# mainboard.net
KiCad netlist of a schematic drawn in EAGLE
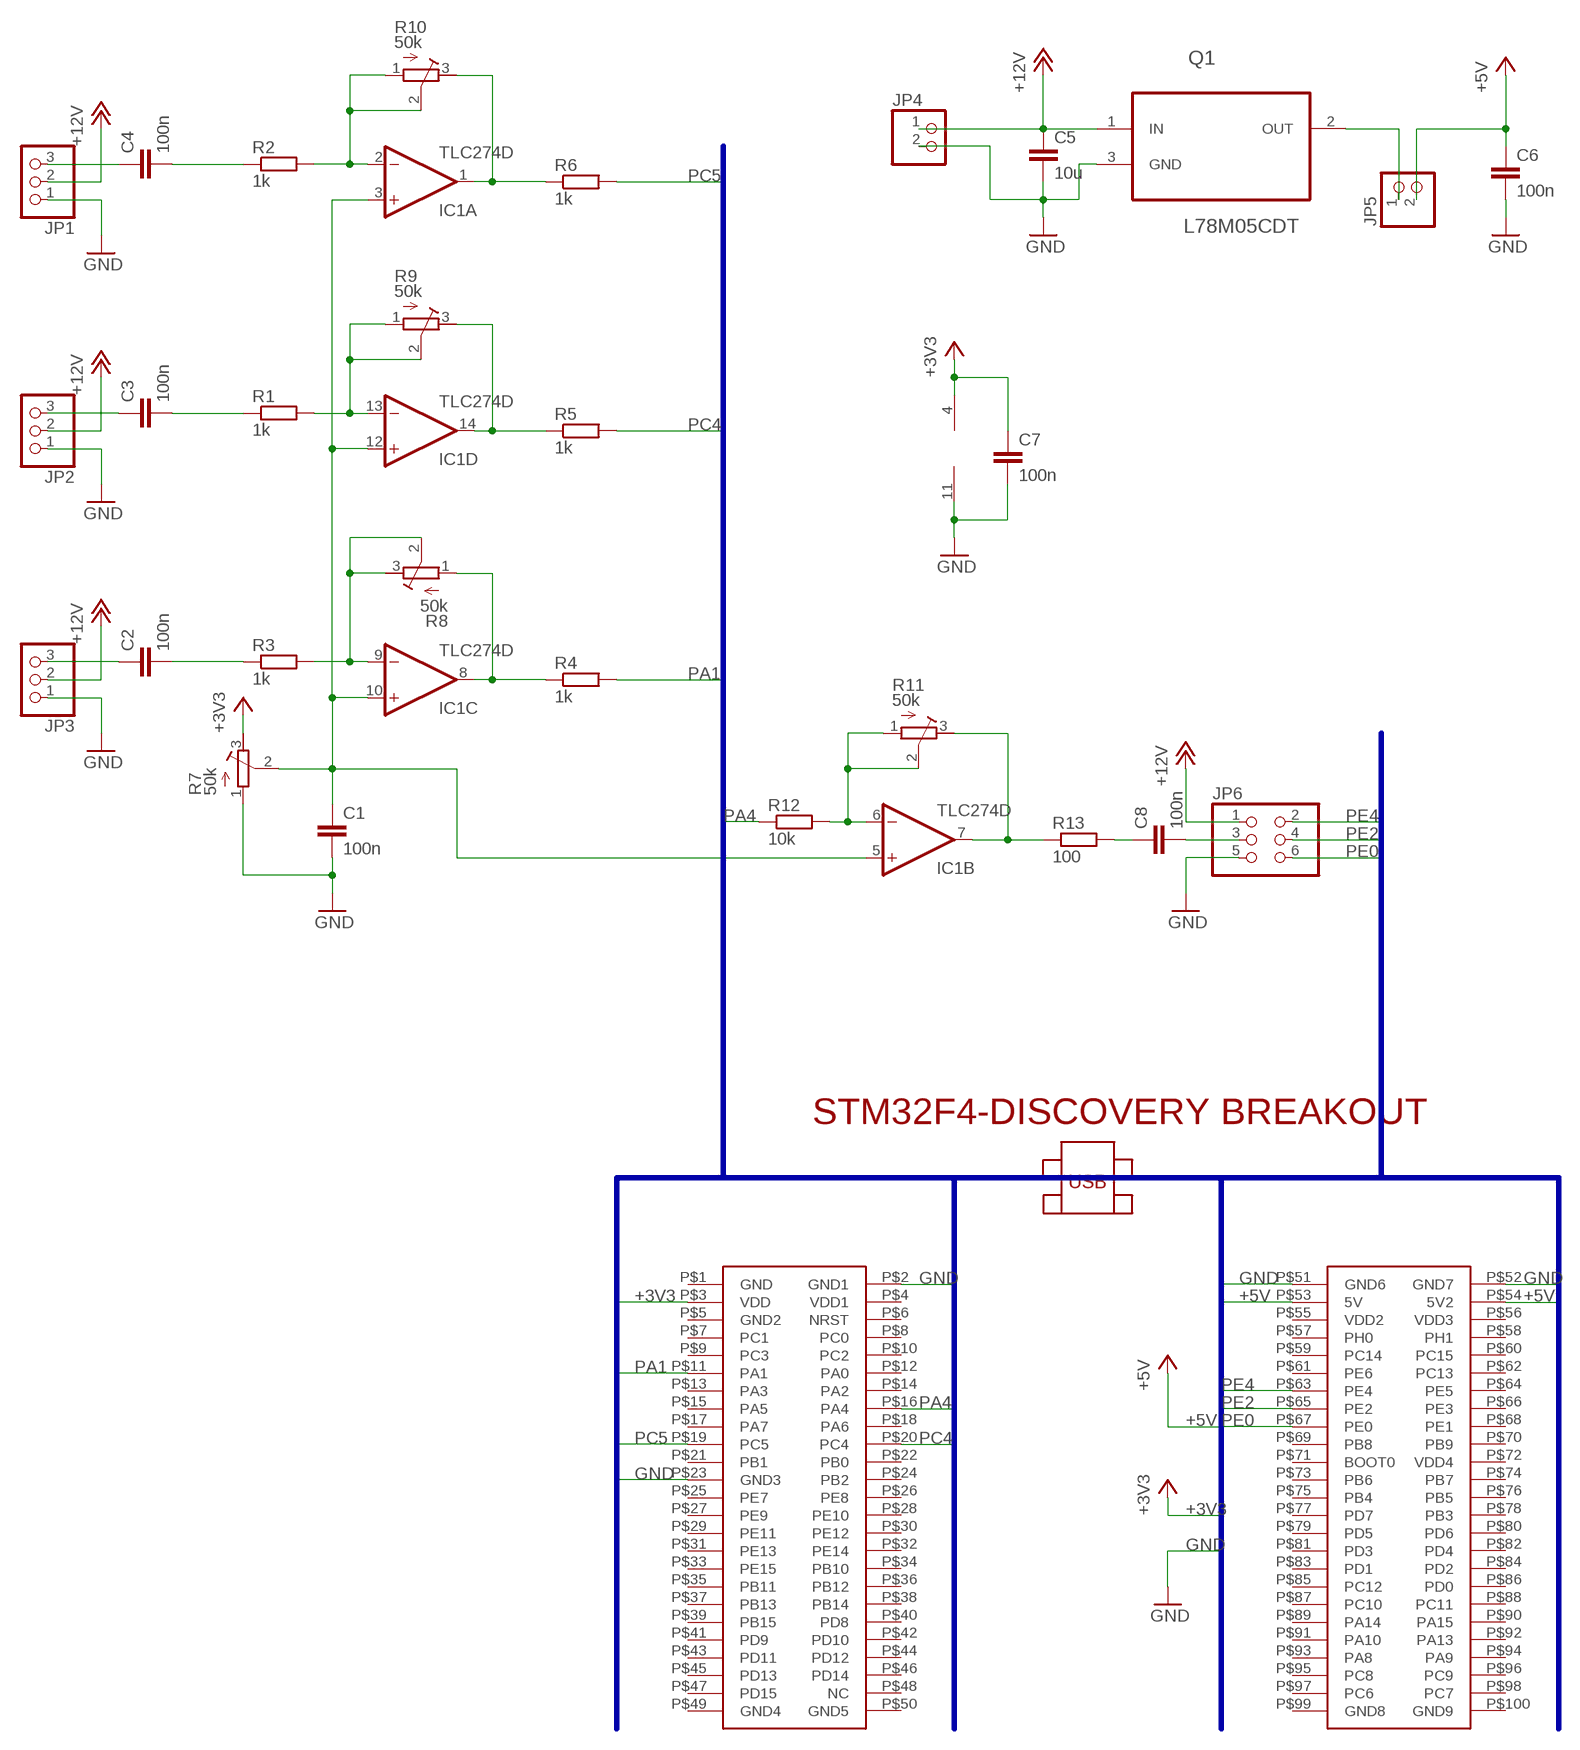
[diagram p0: schematic, sheet 1]

(export (version "E")
  (design (tool "Eeschema 10.0.6"))
  (components
    (comp (ref "C1")
      (value "100n")
      (footprint "eagle-import:C1206K")
      (libsource (lib "eagle-import") (part "C-EUC1206K"))
    )
    (comp (ref "C2")
      (value "100n")
      (footprint "eagle-import:C1206K")
      (libsource (lib "eagle-import") (part "C-EUC1206K"))
    )
    (comp (ref "C3")
      (value "100n")
      (footprint "eagle-import:C1206K")
      (libsource (lib "eagle-import") (part "C-EUC1206K"))
    )
    (comp (ref "C4")
      (value "100n")
      (footprint "eagle-import:C1206K")
      (libsource (lib "eagle-import") (part "C-EUC1206K"))
    )
    (comp (ref "C5")
      (value "10u")
      (footprint "eagle-import:C1206K")
      (libsource (lib "eagle-import") (part "C-EUC1206K"))
    )
    (comp (ref "C6")
      (value "100n")
      (footprint "eagle-import:C1206K")
      (libsource (lib "eagle-import") (part "C-EUC1206K"))
    )
    (comp (ref "C7")
      (value "100n")
      (footprint "eagle-import:C1206K")
      (libsource (lib "eagle-import") (part "C-EUC1206K"))
    )
    (comp (ref "C8")
      (value "100n")
      (footprint "eagle-import:C1206K")
      (libsource (lib "eagle-import") (part "C-EUC1206K"))
    )
    (comp (ref "IC1")
      (value "TLC274D")
      (footprint "eagle-import:SO14")
      (libsource (lib "eagle-import") (part "TLC274D"))
    )
    (comp (ref "JP1")
      (value "PINHD-1X3")
      (footprint "eagle-import:1X03")
      (libsource (lib "eagle-import") (part "PINHD-1X3"))
    )
    (comp (ref "JP2")
      (value "PINHD-1X3")
      (footprint "eagle-import:1X03")
      (libsource (lib "eagle-import") (part "PINHD-1X3"))
    )
    (comp (ref "JP3")
      (value "PINHD-1X3")
      (footprint "eagle-import:1X03")
      (libsource (lib "eagle-import") (part "PINHD-1X3"))
    )
    (comp (ref "JP4")
      (value "PINHD-1X2")
      (footprint "eagle-import:1X02")
      (libsource (lib "eagle-import") (part "PINHD-1X2"))
    )
    (comp (ref "JP5")
      (value "PINHD-1X2")
      (footprint "eagle-import:1X02")
      (libsource (lib "eagle-import") (part "PINHD-1X2"))
    )
    (comp (ref "JP6")
      (value "PINHD-2X3")
      (footprint "eagle-import:2X03")
      (libsource (lib "eagle-import") (part "PINHD-2X3"))
    )
    (comp (ref "Q1")
      (value "L78M05CDT")
      (footprint "eagle-import:TO225P972X240-3N")
      (libsource (lib "eagle-import") (part "L78M05CDT"))
    )
    (comp (ref "R1")
      (value "1k")
      (footprint "eagle-import:M0805")
      (libsource (lib "eagle-import") (part "R-EU_M0805"))
    )
    (comp (ref "R2")
      (value "1k")
      (footprint "eagle-import:M0805")
      (libsource (lib "eagle-import") (part "R-EU_M0805"))
    )
    (comp (ref "R3")
      (value "1k")
      (footprint "eagle-import:M0805")
      (libsource (lib "eagle-import") (part "R-EU_M0805"))
    )
    (comp (ref "R4")
      (value "1k")
      (footprint "eagle-import:M0805")
      (libsource (lib "eagle-import") (part "R-EU_M0805"))
    )
    (comp (ref "R5")
      (value "1k")
      (footprint "eagle-import:R1206")
      (libsource (lib "eagle-import") (part "R-EU_R1206"))
    )
    (comp (ref "R6")
      (value "1k")
      (footprint "eagle-import:M0805")
      (libsource (lib "eagle-import") (part "R-EU_M0805"))
    )
    (comp (ref "R7")
      (value "50k")
      (footprint "eagle-import:RTRIM3314J")
      (libsource (lib "eagle-import") (part "R-TRIMM3314J"))
    )
    (comp (ref "R8")
      (value "50k")
      (footprint "eagle-import:RTRIM3314J")
      (libsource (lib "eagle-import") (part "R-TRIMM3314J"))
    )
    (comp (ref "R9")
      (value "50k")
      (footprint "eagle-import:RTRIM3314J")
      (libsource (lib "eagle-import") (part "R-TRIMM3314J"))
    )
    (comp (ref "R10")
      (value "50k")
      (footprint "eagle-import:RTRIM3314J")
      (libsource (lib "eagle-import") (part "R-TRIMM3314J"))
    )
    (comp (ref "R11")
      (value "50k")
      (footprint "eagle-import:RTRIM3314J")
      (libsource (lib "eagle-import") (part "R-TRIMM3314J"))
    )
    (comp (ref "R12")
      (value "10k")
      (footprint "eagle-import:M1206")
      (libsource (lib "eagle-import") (part "R-EU_M1206"))
    )
    (comp (ref "R13")
      (value "100")
      (footprint "eagle-import:M0805")
      (libsource (lib "eagle-import") (part "R-EU_M0805"))
    )
    (comp (ref "U$1")
      (value "STM32F4-DISCOVERY")
      (footprint "eagle-import:STM32F4-DISCOVERY")
      (libsource (lib "eagle-import") (part "STM32F4-DISCOVERY"))
    )
  )
  (nets
    (net (code "1") (name "+3V3") (class "Default")
      (node (ref "C7") (pin "1") (pinfunction "1_1") (pintype "passive"))
      (node (ref "IC1") (pin "4") (pinfunction "V+_4") (pintype "power_in"))
      (node (ref "R7") (pin "3") (pinfunction "A_3") (pintype "passive"))
      (node (ref "U$1") (pin "P$3") (pinfunction "VDD_P$3") (pintype "bidirectional"))
    )
    (net (code "2") (name "+5V") (class "Default")
      (node (ref "C6") (pin "1") (pinfunction "1_1") (pintype "passive"))
      (node (ref "JP5") (pin "2") (pinfunction "2_2") (pintype "passive"))
      (node (ref "U$1") (pin "P$53") (pinfunction "5V_P$53") (pintype "bidirectional"))
      (node (ref "U$1") (pin "P$54") (pinfunction "5V2_P$54") (pintype "bidirectional"))
    )
    (net (code "3") (name "+12V") (class "Default")
      (node (ref "C5") (pin "1") (pinfunction "1_1") (pintype "passive"))
      (node (ref "JP1") (pin "2") (pinfunction "2_2") (pintype "passive"))
      (node (ref "JP2") (pin "2") (pinfunction "2_2") (pintype "passive"))
      (node (ref "JP3") (pin "2") (pinfunction "2_2") (pintype "passive"))
      (node (ref "JP4") (pin "1") (pinfunction "1_1") (pintype "passive"))
      (node (ref "JP6") (pin "1") (pinfunction "1_1") (pintype "passive"))
      (node (ref "Q1") (pin "1") (pinfunction "IN_1") (pintype "input"))
    )
    (net (code "4") (name "/PA1") (class "Default")
      (node (ref "R4") (pin "2") (pinfunction "2_2") (pintype "passive"))
      (node (ref "U$1") (pin "P$11") (pinfunction "PA1_P$11") (pintype "bidirectional"))
    )
    (net (code "5") (name "/PA4") (class "Default")
      (node (ref "R12") (pin "1") (pinfunction "1_1") (pintype "passive"))
      (node (ref "U$1") (pin "P$16") (pinfunction "PA4_P$16") (pintype "bidirectional"))
    )
    (net (code "6") (name "/PC4") (class "Default")
      (node (ref "R5") (pin "2") (pinfunction "2_2") (pintype "passive"))
      (node (ref "U$1") (pin "P$20") (pinfunction "PC4_P$20") (pintype "bidirectional"))
    )
    (net (code "7") (name "/PC5") (class "Default")
      (node (ref "R6") (pin "2") (pinfunction "2_2") (pintype "passive"))
      (node (ref "U$1") (pin "P$19") (pinfunction "PC5_P$19") (pintype "bidirectional"))
    )
    (net (code "8") (name "/PE0") (class "Default")
      (node (ref "JP6") (pin "6") (pinfunction "6_6") (pintype "passive"))
      (node (ref "U$1") (pin "P$67") (pinfunction "PE0_P$67") (pintype "bidirectional"))
    )
    (net (code "9") (name "/PE2") (class "Default")
      (node (ref "JP6") (pin "4") (pinfunction "4_4") (pintype "passive"))
      (node (ref "U$1") (pin "P$65") (pinfunction "PE2_P$65") (pintype "bidirectional"))
    )
    (net (code "10") (name "/PE4") (class "Default")
      (node (ref "JP6") (pin "2") (pinfunction "2_2") (pintype "passive"))
      (node (ref "U$1") (pin "P$63") (pinfunction "PE4_P$63") (pintype "bidirectional"))
    )
    (net (code "11") (name "GND") (class "Default")
      (node (ref "C1") (pin "2") (pinfunction "2_2") (pintype "passive"))
      (node (ref "C5") (pin "2") (pinfunction "2_2") (pintype "passive"))
      (node (ref "C6") (pin "2") (pinfunction "2_2") (pintype "passive"))
      (node (ref "C7") (pin "2") (pinfunction "2_2") (pintype "passive"))
      (node (ref "IC1") (pin "11") (pinfunction "V-_11") (pintype "power_in"))
      (node (ref "JP1") (pin "1") (pinfunction "1_1") (pintype "passive"))
      (node (ref "JP2") (pin "1") (pinfunction "1_1") (pintype "passive"))
      (node (ref "JP3") (pin "1") (pinfunction "1_1") (pintype "passive"))
      (node (ref "JP4") (pin "2") (pinfunction "2_2") (pintype "passive"))
      (node (ref "JP6") (pin "5") (pinfunction "5_5") (pintype "passive"))
      (node (ref "Q1") (pin "3") (pinfunction "GND_3") (pintype "passive"))
      (node (ref "R7") (pin "1") (pinfunction "E_1") (pintype "passive"))
      (node (ref "U$1") (pin "P$2") (pinfunction "GND1_P$2") (pintype "bidirectional"))
      (node (ref "U$1") (pin "P$23") (pinfunction "GND3_P$23") (pintype "bidirectional"))
      (node (ref "U$1") (pin "P$51") (pinfunction "GND6_P$51") (pintype "bidirectional"))
      (node (ref "U$1") (pin "P$52") (pinfunction "GND7_P$52") (pintype "bidirectional"))
    )
    (net (code "12") (name "Net-(C2-Pad1)") (class "Default")
      (node (ref "C2") (pin "1") (pinfunction "1_1") (pintype "passive"))
      (node (ref "JP3") (pin "3") (pinfunction "3_3") (pintype "passive"))
    )
    (net (code "13") (name "Net-(C2-Pad2)") (class "Default")
      (node (ref "C2") (pin "2") (pinfunction "2_2") (pintype "passive"))
      (node (ref "R3") (pin "1") (pinfunction "1_1") (pintype "passive"))
    )
    (net (code "14") (name "Net-(C3-Pad1)") (class "Default")
      (node (ref "C3") (pin "1") (pinfunction "1_1") (pintype "passive"))
      (node (ref "JP2") (pin "3") (pinfunction "3_3") (pintype "passive"))
    )
    (net (code "15") (name "Net-(C3-Pad2)") (class "Default")
      (node (ref "C3") (pin "2") (pinfunction "2_2") (pintype "passive"))
      (node (ref "R1") (pin "1") (pinfunction "1_1") (pintype "passive"))
    )
    (net (code "16") (name "Net-(C4-Pad1)") (class "Default")
      (node (ref "C4") (pin "1") (pinfunction "1_1") (pintype "passive"))
      (node (ref "JP1") (pin "3") (pinfunction "3_3") (pintype "passive"))
    )
    (net (code "17") (name "Net-(C4-Pad2)") (class "Default")
      (node (ref "C4") (pin "2") (pinfunction "2_2") (pintype "passive"))
      (node (ref "R2") (pin "1") (pinfunction "1_1") (pintype "passive"))
    )
    (net (code "18") (name "Net-(C8-Pad1)") (class "Default")
      (node (ref "C8") (pin "1") (pinfunction "1_1") (pintype "passive"))
      (node (ref "R13") (pin "2") (pinfunction "2_2") (pintype "passive"))
    )
    (net (code "19") (name "Net-(C8-Pad2)") (class "Default")
      (node (ref "C8") (pin "2") (pinfunction "2_2") (pintype "passive"))
      (node (ref "JP6") (pin "3") (pinfunction "3_3") (pintype "passive"))
    )
    (net (code "20") (name "Net-(IC1A-+IN)") (class "Default")
      (node (ref "C1") (pin "1") (pinfunction "1_1") (pintype "passive"))
      (node (ref "IC1") (pin "10") (pinfunction "+IN_10") (pintype "input"))
      (node (ref "IC1") (pin "12") (pinfunction "+IN_12") (pintype "input"))
      (node (ref "IC1") (pin "3") (pinfunction "+IN_3") (pintype "input"))
      (node (ref "IC1") (pin "5") (pinfunction "+IN_5") (pintype "input"))
      (node (ref "R7") (pin "2") (pinfunction "S_2") (pintype "passive"))
    )
    (net (code "21") (name "Net-(IC1A--IN)") (class "Default")
      (node (ref "IC1") (pin "2") (pinfunction "-IN_2") (pintype "input"))
      (node (ref "R10") (pin "1") (pinfunction "E_1") (pintype "passive"))
      (node (ref "R10") (pin "2") (pinfunction "S_2") (pintype "passive"))
      (node (ref "R2") (pin "2") (pinfunction "2_2") (pintype "passive"))
    )
    (net (code "22") (name "Net-(IC1A-OUT)") (class "Default")
      (node (ref "IC1") (pin "1") (pinfunction "OUT_1") (pintype "output"))
      (node (ref "R10") (pin "3") (pinfunction "A_3") (pintype "passive"))
      (node (ref "R6") (pin "1") (pinfunction "1_1") (pintype "passive"))
    )
    (net (code "23") (name "Net-(IC1B--IN)") (class "Default")
      (node (ref "IC1") (pin "6") (pinfunction "-IN_6") (pintype "input"))
      (node (ref "R11") (pin "1") (pinfunction "E_1") (pintype "passive"))
      (node (ref "R11") (pin "2") (pinfunction "S_2") (pintype "passive"))
      (node (ref "R12") (pin "2") (pinfunction "2_2") (pintype "passive"))
    )
    (net (code "24") (name "Net-(IC1B-OUT)") (class "Default")
      (node (ref "IC1") (pin "7") (pinfunction "OUT_7") (pintype "output"))
      (node (ref "R11") (pin "3") (pinfunction "A_3") (pintype "passive"))
      (node (ref "R13") (pin "1") (pinfunction "1_1") (pintype "passive"))
    )
    (net (code "25") (name "Net-(IC1C--IN)") (class "Default")
      (node (ref "IC1") (pin "9") (pinfunction "-IN_9") (pintype "input"))
      (node (ref "R3") (pin "2") (pinfunction "2_2") (pintype "passive"))
      (node (ref "R8") (pin "2") (pinfunction "S_2") (pintype "passive"))
      (node (ref "R8") (pin "3") (pinfunction "A_3") (pintype "passive"))
    )
    (net (code "26") (name "Net-(IC1C-OUT)") (class "Default")
      (node (ref "IC1") (pin "8") (pinfunction "OUT_8") (pintype "output"))
      (node (ref "R4") (pin "1") (pinfunction "1_1") (pintype "passive"))
      (node (ref "R8") (pin "1") (pinfunction "E_1") (pintype "passive"))
    )
    (net (code "27") (name "Net-(IC1D--IN)") (class "Default")
      (node (ref "IC1") (pin "13") (pinfunction "-IN_13") (pintype "input"))
      (node (ref "R1") (pin "2") (pinfunction "2_2") (pintype "passive"))
      (node (ref "R9") (pin "1") (pinfunction "E_1") (pintype "passive"))
      (node (ref "R9") (pin "2") (pinfunction "S_2") (pintype "passive"))
    )
    (net (code "28") (name "Net-(IC1D-OUT)") (class "Default")
      (node (ref "IC1") (pin "14") (pinfunction "OUT_14") (pintype "output"))
      (node (ref "R5") (pin "1") (pinfunction "1_1") (pintype "passive"))
      (node (ref "R9") (pin "3") (pinfunction "A_3") (pintype "passive"))
    )
    (net (code "29") (name "Net-(Q1-OUT)") (class "Default")
      (node (ref "JP5") (pin "1") (pinfunction "1_1") (pintype "passive"))
      (node (ref "Q1") (pin "2") (pinfunction "OUT_2") (pintype "output"))
    )
    (net (code "30") (name "unconnected-(U$1-BOOT0-PadP$71)") (class "Default")
      (node (ref "U$1") (pin "P$71") (pinfunction "BOOT0_P$71") (pintype "bidirectional"))
    )
    (net (code "31") (name "unconnected-(U$1-GND-PadP$1)") (class "Default")
      (node (ref "U$1") (pin "P$1") (pinfunction "GND_P$1") (pintype "bidirectional"))
    )
    (net (code "32") (name "unconnected-(U$1-GND2-PadP$5)") (class "Default")
      (node (ref "U$1") (pin "P$5") (pinfunction "GND2_P$5") (pintype "bidirectional"))
    )
    (net (code "33") (name "unconnected-(U$1-GND4-PadP$49)") (class "Default")
      (node (ref "U$1") (pin "P$49") (pinfunction "GND4_P$49") (pintype "bidirectional"))
    )
    (net (code "34") (name "unconnected-(U$1-GND5-PadP$50)") (class "Default")
      (node (ref "U$1") (pin "P$50") (pinfunction "GND5_P$50") (pintype "bidirectional"))
    )
    (net (code "35") (name "unconnected-(U$1-GND8-PadP$99)") (class "Default")
      (node (ref "U$1") (pin "P$99") (pinfunction "GND8_P$99") (pintype "bidirectional"))
    )
    (net (code "36") (name "unconnected-(U$1-GND9-PadP$100)") (class "Default")
      (node (ref "U$1") (pin "P$100") (pinfunction "GND9_P$100") (pintype "bidirectional"))
    )
    (net (code "37") (name "unconnected-(U$1-NC-PadP$48)") (class "Default")
      (node (ref "U$1") (pin "P$48") (pinfunction "NC_P$48") (pintype "bidirectional"))
    )
    (net (code "38") (name "unconnected-(U$1-NRST-PadP$6)") (class "Default")
      (node (ref "U$1") (pin "P$6") (pinfunction "NRST_P$6") (pintype "bidirectional"))
    )
    (net (code "39") (name "unconnected-(U$1-PA0-PadP$12)") (class "Default")
      (node (ref "U$1") (pin "P$12") (pinfunction "PA0_P$12") (pintype "bidirectional"))
    )
    (net (code "40") (name "unconnected-(U$1-PA2-PadP$14)") (class "Default")
      (node (ref "U$1") (pin "P$14") (pinfunction "PA2_P$14") (pintype "bidirectional"))
    )
    (net (code "41") (name "unconnected-(U$1-PA3-PadP$13)") (class "Default")
      (node (ref "U$1") (pin "P$13") (pinfunction "PA3_P$13") (pintype "bidirectional"))
    )
    (net (code "42") (name "unconnected-(U$1-PA5-PadP$15)") (class "Default")
      (node (ref "U$1") (pin "P$15") (pinfunction "PA5_P$15") (pintype "bidirectional"))
    )
    (net (code "43") (name "unconnected-(U$1-PA6-PadP$18)") (class "Default")
      (node (ref "U$1") (pin "P$18") (pinfunction "PA6_P$18") (pintype "bidirectional"))
    )
    (net (code "44") (name "unconnected-(U$1-PA7-PadP$17)") (class "Default")
      (node (ref "U$1") (pin "P$17") (pinfunction "PA7_P$17") (pintype "bidirectional"))
    )
    (net (code "45") (name "unconnected-(U$1-PA8-PadP$93)") (class "Default")
      (node (ref "U$1") (pin "P$93") (pinfunction "PA8_P$93") (pintype "bidirectional"))
    )
    (net (code "46") (name "unconnected-(U$1-PA9-PadP$94)") (class "Default")
      (node (ref "U$1") (pin "P$94") (pinfunction "PA9_P$94") (pintype "bidirectional"))
    )
    (net (code "47") (name "unconnected-(U$1-PA10-PadP$91)") (class "Default")
      (node (ref "U$1") (pin "P$91") (pinfunction "PA10_P$91") (pintype "bidirectional"))
    )
    (net (code "48") (name "unconnected-(U$1-PA13-PadP$92)") (class "Default")
      (node (ref "U$1") (pin "P$92") (pinfunction "PA13_P$92") (pintype "bidirectional"))
    )
    (net (code "49") (name "unconnected-(U$1-PA14-PadP$89)") (class "Default")
      (node (ref "U$1") (pin "P$89") (pinfunction "PA14_P$89") (pintype "bidirectional"))
    )
    (net (code "50") (name "unconnected-(U$1-PA15-PadP$90)") (class "Default")
      (node (ref "U$1") (pin "P$90") (pinfunction "PA15_P$90") (pintype "bidirectional"))
    )
    (net (code "51") (name "unconnected-(U$1-PB0-PadP$22)") (class "Default")
      (node (ref "U$1") (pin "P$22") (pinfunction "PB0_P$22") (pintype "bidirectional"))
    )
    (net (code "52") (name "unconnected-(U$1-PB1-PadP$21)") (class "Default")
      (node (ref "U$1") (pin "P$21") (pinfunction "PB1_P$21") (pintype "bidirectional"))
    )
    (net (code "53") (name "unconnected-(U$1-PB2-PadP$24)") (class "Default")
      (node (ref "U$1") (pin "P$24") (pinfunction "PB2_P$24") (pintype "bidirectional"))
    )
    (net (code "54") (name "unconnected-(U$1-PB3-PadP$78)") (class "Default")
      (node (ref "U$1") (pin "P$78") (pinfunction "PB3_P$78") (pintype "bidirectional"))
    )
    (net (code "55") (name "unconnected-(U$1-PB4-PadP$75)") (class "Default")
      (node (ref "U$1") (pin "P$75") (pinfunction "PB4_P$75") (pintype "bidirectional"))
    )
    (net (code "56") (name "unconnected-(U$1-PB5-PadP$76)") (class "Default")
      (node (ref "U$1") (pin "P$76") (pinfunction "PB5_P$76") (pintype "bidirectional"))
    )
    (net (code "57") (name "unconnected-(U$1-PB6-PadP$73)") (class "Default")
      (node (ref "U$1") (pin "P$73") (pinfunction "PB6_P$73") (pintype "bidirectional"))
    )
    (net (code "58") (name "unconnected-(U$1-PB7-PadP$74)") (class "Default")
      (node (ref "U$1") (pin "P$74") (pinfunction "PB7_P$74") (pintype "bidirectional"))
    )
    (net (code "59") (name "unconnected-(U$1-PB8-PadP$69)") (class "Default")
      (node (ref "U$1") (pin "P$69") (pinfunction "PB8_P$69") (pintype "bidirectional"))
    )
    (net (code "60") (name "unconnected-(U$1-PB9-PadP$70)") (class "Default")
      (node (ref "U$1") (pin "P$70") (pinfunction "PB9_P$70") (pintype "bidirectional"))
    )
    (net (code "61") (name "unconnected-(U$1-PB10-PadP$34)") (class "Default")
      (node (ref "U$1") (pin "P$34") (pinfunction "PB10_P$34") (pintype "bidirectional"))
    )
    (net (code "62") (name "unconnected-(U$1-PB11-PadP$35)") (class "Default")
      (node (ref "U$1") (pin "P$35") (pinfunction "PB11_P$35") (pintype "bidirectional"))
    )
    (net (code "63") (name "unconnected-(U$1-PB12-PadP$36)") (class "Default")
      (node (ref "U$1") (pin "P$36") (pinfunction "PB12_P$36") (pintype "bidirectional"))
    )
    (net (code "64") (name "unconnected-(U$1-PB13-PadP$37)") (class "Default")
      (node (ref "U$1") (pin "P$37") (pinfunction "PB13_P$37") (pintype "bidirectional"))
    )
    (net (code "65") (name "unconnected-(U$1-PB14-PadP$38)") (class "Default")
      (node (ref "U$1") (pin "P$38") (pinfunction "PB14_P$38") (pintype "bidirectional"))
    )
    (net (code "66") (name "unconnected-(U$1-PB15-PadP$39)") (class "Default")
      (node (ref "U$1") (pin "P$39") (pinfunction "PB15_P$39") (pintype "bidirectional"))
    )
    (net (code "67") (name "unconnected-(U$1-PC0-PadP$8)") (class "Default")
      (node (ref "U$1") (pin "P$8") (pinfunction "PC0_P$8") (pintype "bidirectional"))
    )
    (net (code "68") (name "unconnected-(U$1-PC1-PadP$7)") (class "Default")
      (node (ref "U$1") (pin "P$7") (pinfunction "PC1_P$7") (pintype "bidirectional"))
    )
    (net (code "69") (name "unconnected-(U$1-PC2-PadP$10)") (class "Default")
      (node (ref "U$1") (pin "P$10") (pinfunction "PC2_P$10") (pintype "bidirectional"))
    )
    (net (code "70") (name "unconnected-(U$1-PC3-PadP$9)") (class "Default")
      (node (ref "U$1") (pin "P$9") (pinfunction "PC3_P$9") (pintype "bidirectional"))
    )
    (net (code "71") (name "unconnected-(U$1-PC6-PadP$97)") (class "Default")
      (node (ref "U$1") (pin "P$97") (pinfunction "PC6_P$97") (pintype "bidirectional"))
    )
    (net (code "72") (name "unconnected-(U$1-PC7-PadP$98)") (class "Default")
      (node (ref "U$1") (pin "P$98") (pinfunction "PC7_P$98") (pintype "bidirectional"))
    )
    (net (code "73") (name "unconnected-(U$1-PC8-PadP$95)") (class "Default")
      (node (ref "U$1") (pin "P$95") (pinfunction "PC8_P$95") (pintype "bidirectional"))
    )
    (net (code "74") (name "unconnected-(U$1-PC9-PadP$96)") (class "Default")
      (node (ref "U$1") (pin "P$96") (pinfunction "PC9_P$96") (pintype "bidirectional"))
    )
    (net (code "75") (name "unconnected-(U$1-PC10-PadP$87)") (class "Default")
      (node (ref "U$1") (pin "P$87") (pinfunction "PC10_P$87") (pintype "bidirectional"))
    )
    (net (code "76") (name "unconnected-(U$1-PC11-PadP$88)") (class "Default")
      (node (ref "U$1") (pin "P$88") (pinfunction "PC11_P$88") (pintype "bidirectional"))
    )
    (net (code "77") (name "unconnected-(U$1-PC12-PadP$85)") (class "Default")
      (node (ref "U$1") (pin "P$85") (pinfunction "PC12_P$85") (pintype "bidirectional"))
    )
    (net (code "78") (name "unconnected-(U$1-PC13-PadP$62)") (class "Default")
      (node (ref "U$1") (pin "P$62") (pinfunction "PC13_P$62") (pintype "bidirectional"))
    )
    (net (code "79") (name "unconnected-(U$1-PC14-PadP$59)") (class "Default")
      (node (ref "U$1") (pin "P$59") (pinfunction "PC14_P$59") (pintype "bidirectional"))
    )
    (net (code "80") (name "unconnected-(U$1-PC15-PadP$60)") (class "Default")
      (node (ref "U$1") (pin "P$60") (pinfunction "PC15_P$60") (pintype "bidirectional"))
    )
    (net (code "81") (name "unconnected-(U$1-PD0-PadP$86)") (class "Default")
      (node (ref "U$1") (pin "P$86") (pinfunction "PD0_P$86") (pintype "bidirectional"))
    )
    (net (code "82") (name "unconnected-(U$1-PD1-PadP$83)") (class "Default")
      (node (ref "U$1") (pin "P$83") (pinfunction "PD1_P$83") (pintype "bidirectional"))
    )
    (net (code "83") (name "unconnected-(U$1-PD2-PadP$84)") (class "Default")
      (node (ref "U$1") (pin "P$84") (pinfunction "PD2_P$84") (pintype "bidirectional"))
    )
    (net (code "84") (name "unconnected-(U$1-PD3-PadP$81)") (class "Default")
      (node (ref "U$1") (pin "P$81") (pinfunction "PD3_P$81") (pintype "bidirectional"))
    )
    (net (code "85") (name "unconnected-(U$1-PD4-PadP$82)") (class "Default")
      (node (ref "U$1") (pin "P$82") (pinfunction "PD4_P$82") (pintype "bidirectional"))
    )
    (net (code "86") (name "unconnected-(U$1-PD5-PadP$79)") (class "Default")
      (node (ref "U$1") (pin "P$79") (pinfunction "PD5_P$79") (pintype "bidirectional"))
    )
    (net (code "87") (name "unconnected-(U$1-PD6-PadP$80)") (class "Default")
      (node (ref "U$1") (pin "P$80") (pinfunction "PD6_P$80") (pintype "bidirectional"))
    )
    (net (code "88") (name "unconnected-(U$1-PD7-PadP$77)") (class "Default")
      (node (ref "U$1") (pin "P$77") (pinfunction "PD7_P$77") (pintype "bidirectional"))
    )
    (net (code "89") (name "unconnected-(U$1-PD8-PadP$40)") (class "Default")
      (node (ref "U$1") (pin "P$40") (pinfunction "PD8_P$40") (pintype "bidirectional"))
    )
    (net (code "90") (name "unconnected-(U$1-PD9-PadP$41)") (class "Default")
      (node (ref "U$1") (pin "P$41") (pinfunction "PD9_P$41") (pintype "bidirectional"))
    )
    (net (code "91") (name "unconnected-(U$1-PD10-PadP$42)") (class "Default")
      (node (ref "U$1") (pin "P$42") (pinfunction "PD10_P$42") (pintype "bidirectional"))
    )
    (net (code "92") (name "unconnected-(U$1-PD11-PadP$43)") (class "Default")
      (node (ref "U$1") (pin "P$43") (pinfunction "PD11_P$43") (pintype "bidirectional"))
    )
    (net (code "93") (name "unconnected-(U$1-PD12-PadP$44)") (class "Default")
      (node (ref "U$1") (pin "P$44") (pinfunction "PD12_P$44") (pintype "bidirectional"))
    )
    (net (code "94") (name "unconnected-(U$1-PD13-PadP$45)") (class "Default")
      (node (ref "U$1") (pin "P$45") (pinfunction "PD13_P$45") (pintype "bidirectional"))
    )
    (net (code "95") (name "unconnected-(U$1-PD14-PadP$46)") (class "Default")
      (node (ref "U$1") (pin "P$46") (pinfunction "PD14_P$46") (pintype "bidirectional"))
    )
    (net (code "96") (name "unconnected-(U$1-PD15-PadP$47)") (class "Default")
      (node (ref "U$1") (pin "P$47") (pinfunction "PD15_P$47") (pintype "bidirectional"))
    )
    (net (code "97") (name "unconnected-(U$1-PE1-PadP$68)") (class "Default")
      (node (ref "U$1") (pin "P$68") (pinfunction "PE1_P$68") (pintype "bidirectional"))
    )
    (net (code "98") (name "unconnected-(U$1-PE3-PadP$66)") (class "Default")
      (node (ref "U$1") (pin "P$66") (pinfunction "PE3_P$66") (pintype "bidirectional"))
    )
    (net (code "99") (name "unconnected-(U$1-PE5-PadP$64)") (class "Default")
      (node (ref "U$1") (pin "P$64") (pinfunction "PE5_P$64") (pintype "bidirectional"))
    )
    (net (code "100") (name "unconnected-(U$1-PE6-PadP$61)") (class "Default")
      (node (ref "U$1") (pin "P$61") (pinfunction "PE6_P$61") (pintype "bidirectional"))
    )
    (net (code "101") (name "unconnected-(U$1-PE7-PadP$25)") (class "Default")
      (node (ref "U$1") (pin "P$25") (pinfunction "PE7_P$25") (pintype "bidirectional"))
    )
    (net (code "102") (name "unconnected-(U$1-PE8-PadP$26)") (class "Default")
      (node (ref "U$1") (pin "P$26") (pinfunction "PE8_P$26") (pintype "bidirectional"))
    )
    (net (code "103") (name "unconnected-(U$1-PE9-PadP$27)") (class "Default")
      (node (ref "U$1") (pin "P$27") (pinfunction "PE9_P$27") (pintype "bidirectional"))
    )
    (net (code "104") (name "unconnected-(U$1-PE10-PadP$28)") (class "Default")
      (node (ref "U$1") (pin "P$28") (pinfunction "PE10_P$28") (pintype "bidirectional"))
    )
    (net (code "105") (name "unconnected-(U$1-PE11-PadP$29)") (class "Default")
      (node (ref "U$1") (pin "P$29") (pinfunction "PE11_P$29") (pintype "bidirectional"))
    )
    (net (code "106") (name "unconnected-(U$1-PE12-PadP$30)") (class "Default")
      (node (ref "U$1") (pin "P$30") (pinfunction "PE12_P$30") (pintype "bidirectional"))
    )
    (net (code "107") (name "unconnected-(U$1-PE13-PadP$31)") (class "Default")
      (node (ref "U$1") (pin "P$31") (pinfunction "PE13_P$31") (pintype "bidirectional"))
    )
    (net (code "108") (name "unconnected-(U$1-PE14-PadP$32)") (class "Default")
      (node (ref "U$1") (pin "P$32") (pinfunction "PE14_P$32") (pintype "bidirectional"))
    )
    (net (code "109") (name "unconnected-(U$1-PE15-PadP$33)") (class "Default")
      (node (ref "U$1") (pin "P$33") (pinfunction "PE15_P$33") (pintype "bidirectional"))
    )
    (net (code "110") (name "unconnected-(U$1-PH0-PadP$57)") (class "Default")
      (node (ref "U$1") (pin "P$57") (pinfunction "PH0_P$57") (pintype "bidirectional"))
    )
    (net (code "111") (name "unconnected-(U$1-PH1-PadP$58)") (class "Default")
      (node (ref "U$1") (pin "P$58") (pinfunction "PH1_P$58") (pintype "bidirectional"))
    )
    (net (code "112") (name "unconnected-(U$1-VDD1-PadP$4)") (class "Default")
      (node (ref "U$1") (pin "P$4") (pinfunction "VDD1_P$4") (pintype "bidirectional"))
    )
    (net (code "113") (name "unconnected-(U$1-VDD2-PadP$55)") (class "Default")
      (node (ref "U$1") (pin "P$55") (pinfunction "VDD2_P$55") (pintype "bidirectional"))
    )
    (net (code "114") (name "unconnected-(U$1-VDD3-PadP$56)") (class "Default")
      (node (ref "U$1") (pin "P$56") (pinfunction "VDD3_P$56") (pintype "bidirectional"))
    )
    (net (code "115") (name "unconnected-(U$1-VDD4-PadP$72)") (class "Default")
      (node (ref "U$1") (pin "P$72") (pinfunction "VDD4_P$72") (pintype "bidirectional"))
    )
  )
)
